# IRsensor_Relay_Controller.net
KiCad netlist of a schematic drawn in Altium Designer
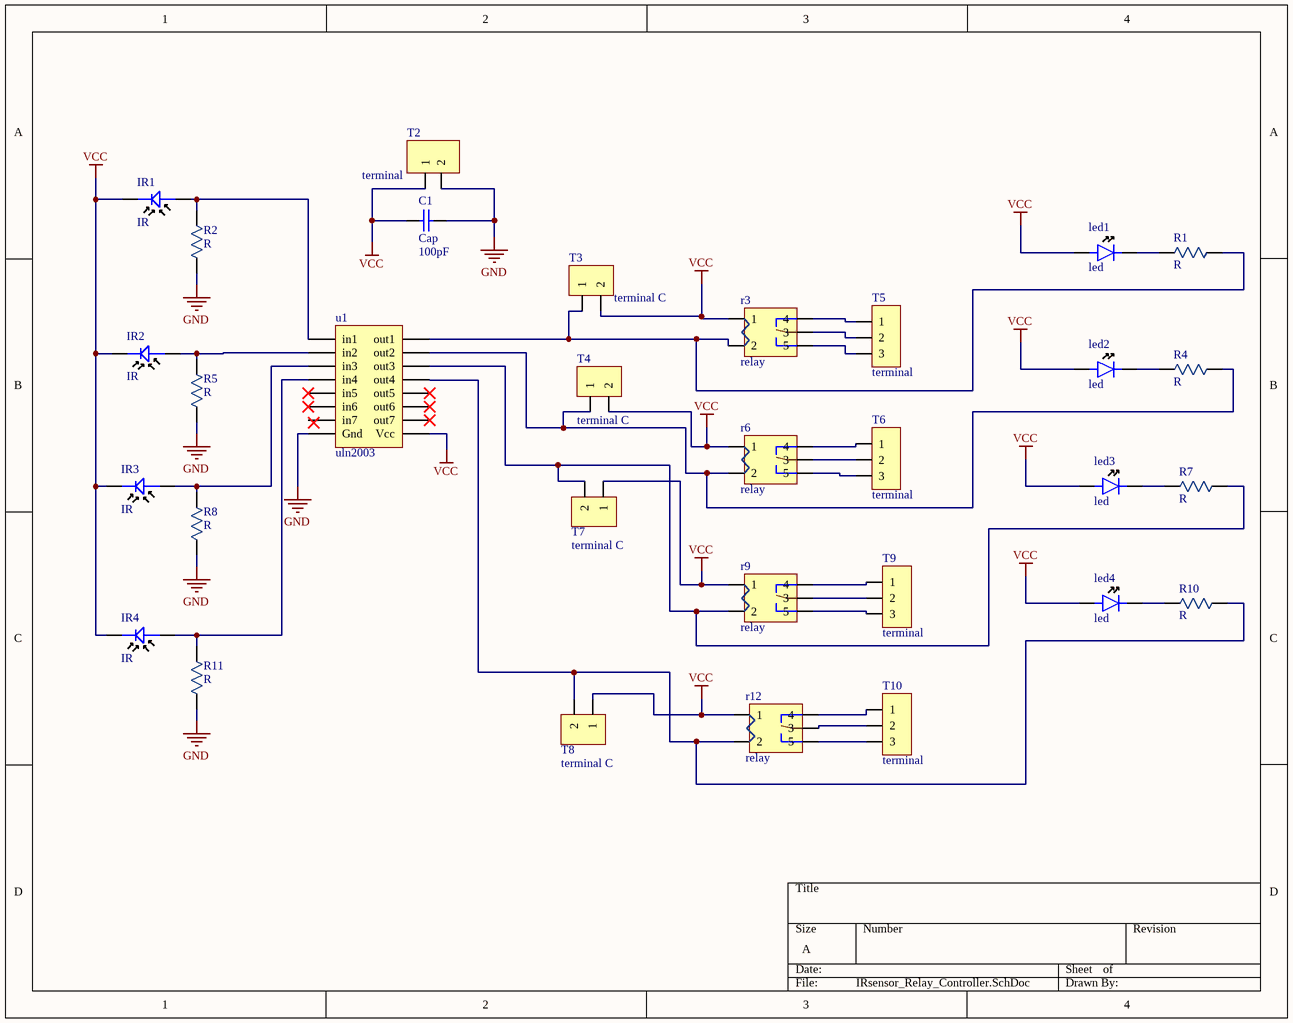
[diagram p0: IRsensor_Relay_Controller.SchDoc]

(export (version "E")
  (design (tool "Eeschema 10.0.6"))
  (components
    (comp (ref "C1")
      (value "Cap")
      (footprint "RAD-0.3")
      (description "Capacitor")
      (fields (field (name "ALTIUM_VALUE") "100pF") (field (name "PUBLISHER") "Altium Limited"))
      (libsource (lib "Miscellaneous Devices") (part "Cap"))
    )
    (comp (ref "IR1")
      (value "IR")
      (footprint "IR sensor")
      (description "EMITTER IR 940NM 100MA RADIAL")
      (fields (field (name "MANUFACTURER") "Everlight") (field (name "MANUFACTURER PART NUMBER") "IR204-A"))
      (libsource (lib "Schlib1") (part "IR204-A"))
    )
    (comp (ref "IR2")
      (value "IR")
      (footprint "IR sensor")
      (description "EMITTER IR 940NM 100MA RADIAL")
      (fields (field (name "MANUFACTURER") "Everlight") (field (name "MANUFACTURER PART NUMBER") "IR204-A"))
      (libsource (lib "Schlib1") (part "IR204-A"))
    )
    (comp (ref "IR3")
      (value "IR")
      (footprint "IR sensor")
      (description "EMITTER IR 940NM 100MA RADIAL")
      (fields (field (name "MANUFACTURER") "Everlight") (field (name "MANUFACTURER PART NUMBER") "IR204-A"))
      (libsource (lib "Schlib1") (part "IR204-A"))
    )
    (comp (ref "IR4")
      (value "IR")
      (footprint "IR sensor")
      (description "EMITTER IR 940NM 100MA RADIAL")
      (fields (field (name "MANUFACTURER") "Everlight") (field (name "MANUFACTURER PART NUMBER") "IR204-A"))
      (libsource (lib "Schlib1") (part "IR204-A"))
    )
    (comp (ref "led1")
      (value "led")
      (footprint "led")
      (description "LED,  5MM,  HIGH EFFICIENCY,  DIFFUSED,  RED")
      (fields (field (name "MANUFACTURER") "Dialight") (field (name "MANUFACTURER PART NUMBER") "521-9240F"))
      (libsource (lib "Schlib1") (part "led"))
    )
    (comp (ref "led2")
      (value "led")
      (footprint "led")
      (description "LED,  5MM,  HIGH EFFICIENCY,  DIFFUSED,  RED")
      (fields (field (name "MANUFACTURER") "Dialight") (field (name "MANUFACTURER PART NUMBER") "521-9240F"))
      (libsource (lib "Schlib1") (part "led"))
    )
    (comp (ref "led3")
      (value "led")
      (footprint "led")
      (description "LED,  5MM,  HIGH EFFICIENCY,  DIFFUSED,  RED")
      (fields (field (name "MANUFACTURER") "Dialight") (field (name "MANUFACTURER PART NUMBER") "521-9240F"))
      (libsource (lib "Schlib1") (part "led"))
    )
    (comp (ref "led4")
      (value "led")
      (footprint "led")
      (description "LED,  5MM,  HIGH EFFICIENCY,  DIFFUSED,  RED")
      (fields (field (name "MANUFACTURER") "Dialight") (field (name "MANUFACTURER PART NUMBER") "521-9240F"))
      (libsource (lib "Schlib1") (part "led"))
    )
    (comp (ref "R1")
      (value "R")
      (footprint "resistor 1/4 watt")
      (description "RES 330 OHM 1/4W 5% AXIAL")
      (fields
        (field (name "MANUFACTURER") "TE Connectivity")
        (field (name "MANUFACTURER PART NUMBER") "CBT25J330R")
      )
      (libsource (lib "Schlib1") (part "resistor 1/4 watt"))
    )
    (comp (ref "R2")
      (value "R")
      (footprint "resistor 1/4 watt")
      (description "RES 330 OHM 1/4W 5% AXIAL")
      (fields
        (field (name "MANUFACTURER") "TE Connectivity")
        (field (name "MANUFACTURER PART NUMBER") "CBT25J330R")
      )
      (libsource (lib "Schlib1") (part "resistor 1/4 watt"))
    )
    (comp (ref "r3")
      (value "relay")
      (footprint "relay 5vdc")
      (fields
        (field (name "MANUFACTURER") "TE Connectivity")
        (field (name "MANUFACTURER PART NUMBER") "V23101-D0007-A201")
      )
      (libsource (lib "Schlib1") (part "relay 5v"))
    )
    (comp (ref "R4")
      (value "R")
      (footprint "resistor 1/4 watt")
      (description "RES 330 OHM 1/4W 5% AXIAL")
      (fields
        (field (name "MANUFACTURER") "TE Connectivity")
        (field (name "MANUFACTURER PART NUMBER") "CBT25J330R")
      )
      (libsource (lib "Schlib1") (part "resistor 1/4 watt"))
    )
    (comp (ref "R5")
      (value "R")
      (footprint "resistor 1/4 watt")
      (description "RES 330 OHM 1/4W 5% AXIAL")
      (fields
        (field (name "MANUFACTURER") "TE Connectivity")
        (field (name "MANUFACTURER PART NUMBER") "CBT25J330R")
      )
      (libsource (lib "Schlib1") (part "resistor 1/4 watt"))
    )
    (comp (ref "r6")
      (value "relay")
      (footprint "relay 5vdc")
      (fields
        (field (name "MANUFACTURER") "TE Connectivity")
        (field (name "MANUFACTURER PART NUMBER") "V23101-D0007-A201")
      )
      (libsource (lib "Schlib1") (part "relay 5v"))
    )
    (comp (ref "R7")
      (value "R")
      (footprint "resistor 1/4 watt")
      (description "RES 330 OHM 1/4W 5% AXIAL")
      (fields
        (field (name "MANUFACTURER") "TE Connectivity")
        (field (name "MANUFACTURER PART NUMBER") "CBT25J330R")
      )
      (libsource (lib "Schlib1") (part "resistor 1/4 watt"))
    )
    (comp (ref "R8")
      (value "R")
      (footprint "resistor 1/4 watt")
      (description "RES 330 OHM 1/4W 5% AXIAL")
      (fields
        (field (name "MANUFACTURER") "TE Connectivity")
        (field (name "MANUFACTURER PART NUMBER") "CBT25J330R")
      )
      (libsource (lib "Schlib1") (part "resistor 1/4 watt"))
    )
    (comp (ref "r9")
      (value "relay")
      (footprint "relay 5vdc")
      (fields
        (field (name "MANUFACTURER") "TE Connectivity")
        (field (name "MANUFACTURER PART NUMBER") "V23101-D0007-A201")
      )
      (libsource (lib "Schlib1") (part "relay 5v"))
    )
    (comp (ref "R10")
      (value "R")
      (footprint "resistor 1/4 watt")
      (description "RES 330 OHM 1/4W 5% AXIAL")
      (fields
        (field (name "MANUFACTURER") "TE Connectivity")
        (field (name "MANUFACTURER PART NUMBER") "CBT25J330R")
      )
      (libsource (lib "Schlib1") (part "resistor 1/4 watt"))
    )
    (comp (ref "R11")
      (value "R")
      (footprint "resistor 1/4 watt")
      (description "RES 330 OHM 1/4W 5% AXIAL")
      (fields
        (field (name "MANUFACTURER") "TE Connectivity")
        (field (name "MANUFACTURER PART NUMBER") "CBT25J330R")
      )
      (libsource (lib "Schlib1") (part "resistor 1/4 watt"))
    )
    (comp (ref "r12")
      (value "relay")
      (footprint "relay 5vdc")
      (fields
        (field (name "MANUFACTURER") "TE Connectivity")
        (field (name "MANUFACTURER PART NUMBER") "V23101-D0007-A201")
      )
      (libsource (lib "Schlib1") (part "relay 5v"))
    )
    (comp (ref "T2")
      (value "terminal")
      (footprint "terminal 2pin")
      (description "PCB Terminal Block 3 Poles, 5 mm Pitch, 691101710003, Würth Elektronik")
      (fields
        (field (name "MANUFACTURER") "Wurth Electronics")
        (field (name "MANUFACTURER PART NUMBER") "691101710003")
      )
      (libsource (lib "Schlib1") (part "terminal 2pin"))
    )
    (comp (ref "T3")
      (value "terminal C")
      (footprint "terminal C 2pin")
      (description ".100 TERMINAL ASSEMBLY")
      (fields
        (field (name "MANUFACTURER") "Samtec")
        (field (name "MANUFACTURER PART NUMBER") "IPL1-102-01-S-S-RA-K")
      )
      (libsource (lib "") (part "terminal Cu_1"))
    )
    (comp (ref "T4")
      (value "terminal C")
      (footprint "terminal C 2pin")
      (description ".100 TERMINAL ASSEMBLY")
      (fields
        (field (name "MANUFACTURER") "Samtec")
        (field (name "MANUFACTURER PART NUMBER") "IPL1-102-01-S-S-RA-K")
      )
      (libsource (lib "") (part "terminal Cu_1"))
    )
    (comp (ref "T5")
      (value "terminal")
      (footprint "terminal 3pin")
      (description "Conn Mini-Power Terminal Strip HDR 12 POS 2.54mm Solder ST SMD 12 Terminal 1 Port")
      (fields
        (field (name "MANUFACTURER") "Samtec")
        (field (name "MANUFACTURER PART NUMBER") "IPL1-106-02-L-D-K")
      )
      (libsource (lib "Schlib1") (part "terminal 3pin"))
    )
    (comp (ref "T6")
      (value "terminal")
      (footprint "terminal 3pin")
      (description "Conn Mini-Power Terminal Strip HDR 12 POS 2.54mm Solder ST SMD 12 Terminal 1 Port")
      (fields
        (field (name "MANUFACTURER") "Samtec")
        (field (name "MANUFACTURER PART NUMBER") "IPL1-106-02-L-D-K")
      )
      (libsource (lib "Schlib1") (part "terminal 3pin"))
    )
    (comp (ref "T7")
      (value "terminal C")
      (footprint "terminal C 2pin")
      (description ".100 TERMINAL ASSEMBLY")
      (fields
        (field (name "MANUFACTURER") "Samtec")
        (field (name "MANUFACTURER PART NUMBER") "IPL1-102-01-S-S-RA-K")
      )
      (libsource (lib "Schlib1") (part "terminal Cu"))
    )
    (comp (ref "T8")
      (value "terminal C")
      (footprint "terminal C 2pin")
      (description ".100 TERMINAL ASSEMBLY")
      (fields
        (field (name "MANUFACTURER") "Samtec")
        (field (name "MANUFACTURER PART NUMBER") "IPL1-102-01-S-S-RA-K")
      )
      (libsource (lib "Schlib1") (part "terminal Cu"))
    )
    (comp (ref "T9")
      (value "terminal")
      (footprint "terminal 3pin")
      (description "Conn Mini-Power Terminal Strip HDR 12 POS 2.54mm Solder ST SMD 12 Terminal 1 Port")
      (fields
        (field (name "MANUFACTURER") "Samtec")
        (field (name "MANUFACTURER PART NUMBER") "IPL1-106-02-L-D-K")
      )
      (libsource (lib "Schlib1") (part "terminal 3pin"))
    )
    (comp (ref "T10")
      (value "terminal")
      (footprint "terminal 3pin")
      (description "Conn Mini-Power Terminal Strip HDR 12 POS 2.54mm Solder ST SMD 12 Terminal 1 Port")
      (fields
        (field (name "MANUFACTURER") "Samtec")
        (field (name "MANUFACTURER PART NUMBER") "IPL1-106-02-L-D-K")
      )
      (libsource (lib "Schlib1") (part "terminal 3pin"))
    )
    (comp (ref "u1")
      (value "uln2003")
      (footprint "uln2003")
      (description "TEXAS INSTRUMENTS - ULN2003ADR - Bipolar Transistor Array, Darlington, NPN, 50 V, 350 mA, SOIC")
      (fields
        (field (name "MANUFACTURER") "Texas Instruments")
        (field (name "MANUFACTURER PART NUMBER") "ULN2003ADR")
      )
      (libsource (lib "Schlib1") (part "ULN2003ADR"))
    )
  )
  (nets
    (net (code "1") (name "GND") (class "Default")
      (node (ref "C1") (pin "2") (pinfunction "2_2") (pintype "passive"))
      (node (ref "R11") (pin "2") (pinfunction "2_2") (pintype "passive"))
      (node (ref "R2") (pin "2") (pinfunction "2_2") (pintype "passive"))
      (node (ref "R5") (pin "2") (pinfunction "2_2") (pintype "passive"))
      (node (ref "R8") (pin "2") (pinfunction "2_2") (pintype "passive"))
      (node (ref "T2") (pin "2") (pinfunction "2_2") (pintype "passive"))
      (node (ref "u1") (pin "Vcc") (pinfunction "Gnd_Vcc") (pintype "passive"))
    )
    (net (code "2") (name "Net-(IR1-Pad+)") (class "Default")
      (node (ref "IR1") (pin "+") (pinfunction "+_+") (pintype "passive"))
      (node (ref "R2") (pin "1") (pinfunction "1_1") (pintype "passive"))
      (node (ref "u1") (pin "in1") (pinfunction "in1_in1") (pintype "passive"))
    )
    (net (code "3") (name "Net-(IR2-Pad+)") (class "Default")
      (node (ref "IR2") (pin "+") (pinfunction "+_+") (pintype "passive"))
      (node (ref "R5") (pin "1") (pinfunction "1_1") (pintype "passive"))
      (node (ref "u1") (pin "in2") (pinfunction "in2_in2") (pintype "passive"))
    )
    (net (code "4") (name "Net-(IR3-Pad+)") (class "Default")
      (node (ref "IR3") (pin "+") (pinfunction "+_+") (pintype "passive"))
      (node (ref "R8") (pin "1") (pinfunction "1_1") (pintype "passive"))
      (node (ref "u1") (pin "in3") (pinfunction "in3_in3") (pintype "passive"))
    )
    (net (code "5") (name "Net-(IR4-Pad+)") (class "Default")
      (node (ref "IR4") (pin "+") (pinfunction "+_+") (pintype "passive"))
      (node (ref "R11") (pin "1") (pinfunction "1_1") (pintype "passive"))
      (node (ref "u1") (pin "in4") (pinfunction "in4_in4") (pintype "passive"))
    )
    (net (code "6") (name "Net-(R1-Pad1)") (class "Default")
      (node (ref "R1") (pin "1") (pinfunction "1_1") (pintype "passive"))
      (node (ref "led1") (pin "-") (pinfunction "-_-") (pintype "passive"))
    )
    (net (code "7") (name "Net-(R1-Pad2)") (class "Default")
      (node (ref "R1") (pin "2") (pinfunction "2_2") (pintype "passive"))
      (node (ref "T3") (pin "1") (pinfunction "1_1") (pintype "passive"))
      (node (ref "r3") (pin "2") (pinfunction "2_2") (pintype "passive"))
      (node (ref "u1") (pin "out1") (pinfunction "out1_out1") (pintype "passive"))
    )
    (net (code "8") (name "Net-(R4-Pad1)") (class "Default")
      (node (ref "R4") (pin "1") (pinfunction "1_1") (pintype "passive"))
      (node (ref "led2") (pin "-") (pinfunction "-_-") (pintype "passive"))
    )
    (net (code "9") (name "Net-(R4-Pad2)") (class "Default")
      (node (ref "R4") (pin "2") (pinfunction "2_2") (pintype "passive"))
      (node (ref "T4") (pin "1") (pinfunction "1_1") (pintype "passive"))
      (node (ref "r6") (pin "2") (pinfunction "2_2") (pintype "passive"))
      (node (ref "u1") (pin "out2") (pinfunction "out2_out2") (pintype "passive"))
    )
    (net (code "10") (name "Net-(R7-Pad1)") (class "Default")
      (node (ref "R7") (pin "1") (pinfunction "1_1") (pintype "passive"))
      (node (ref "led3") (pin "-") (pinfunction "-_-") (pintype "passive"))
    )
    (net (code "11") (name "Net-(R7-Pad2)") (class "Default")
      (node (ref "R7") (pin "2") (pinfunction "2_2") (pintype "passive"))
      (node (ref "T7") (pin "2") (pinfunction "2_2") (pintype "passive"))
      (node (ref "r9") (pin "2") (pinfunction "2_2") (pintype "passive"))
      (node (ref "u1") (pin "out3") (pinfunction "out3_out3") (pintype "passive"))
    )
    (net (code "12") (name "Net-(R10-Pad1)") (class "Default")
      (node (ref "R10") (pin "1") (pinfunction "1_1") (pintype "passive"))
      (node (ref "led4") (pin "-") (pinfunction "-_-") (pintype "passive"))
    )
    (net (code "13") (name "Net-(R10-Pad2)") (class "Default")
      (node (ref "R10") (pin "2") (pinfunction "2_2") (pintype "passive"))
      (node (ref "T8") (pin "2") (pinfunction "2_2") (pintype "passive"))
      (node (ref "r12") (pin "2") (pinfunction "2_2") (pintype "passive"))
      (node (ref "u1") (pin "out4") (pinfunction "out4_out4") (pintype "passive"))
    )
    (net (code "14") (name "Net-(T5-Pad1)") (class "Default")
      (node (ref "T5") (pin "1") (pinfunction "1_1") (pintype "passive"))
      (node (ref "r3") (pin "4") (pinfunction "4_4") (pintype "passive"))
    )
    (net (code "15") (name "Net-(T5-Pad2)") (class "Default")
      (node (ref "T5") (pin "2") (pinfunction "2_2") (pintype "passive"))
      (node (ref "r3") (pin "3") (pinfunction "3_3") (pintype "passive"))
    )
    (net (code "16") (name "Net-(T5-Pad3)") (class "Default")
      (node (ref "T5") (pin "3") (pinfunction "3_3") (pintype "passive"))
      (node (ref "r3") (pin "5") (pinfunction "5_5") (pintype "passive"))
    )
    (net (code "17") (name "Net-(T6-Pad1)") (class "Default")
      (node (ref "T6") (pin "1") (pinfunction "1_1") (pintype "passive"))
      (node (ref "r6") (pin "4") (pinfunction "4_4") (pintype "passive"))
    )
    (net (code "18") (name "Net-(T6-Pad2)") (class "Default")
      (node (ref "T6") (pin "2") (pinfunction "2_2") (pintype "passive"))
      (node (ref "r6") (pin "3") (pinfunction "3_3") (pintype "passive"))
    )
    (net (code "19") (name "Net-(T6-Pad3)") (class "Default")
      (node (ref "T6") (pin "3") (pinfunction "3_3") (pintype "passive"))
      (node (ref "r6") (pin "5") (pinfunction "5_5") (pintype "passive"))
    )
    (net (code "20") (name "Net-(T9-Pad1)") (class "Default")
      (node (ref "T9") (pin "1") (pinfunction "1_1") (pintype "passive"))
      (node (ref "r9") (pin "4") (pinfunction "4_4") (pintype "passive"))
    )
    (net (code "21") (name "Net-(T9-Pad2)") (class "Default")
      (node (ref "T9") (pin "2") (pinfunction "2_2") (pintype "passive"))
      (node (ref "r9") (pin "3") (pinfunction "3_3") (pintype "passive"))
    )
    (net (code "22") (name "Net-(T9-Pad3)") (class "Default")
      (node (ref "T9") (pin "3") (pinfunction "3_3") (pintype "passive"))
      (node (ref "r9") (pin "5") (pinfunction "5_5") (pintype "passive"))
    )
    (net (code "23") (name "Net-(T10-Pad1)") (class "Default")
      (node (ref "T10") (pin "1") (pinfunction "1_1") (pintype "passive"))
      (node (ref "r12") (pin "4") (pinfunction "4_4") (pintype "passive"))
    )
    (net (code "24") (name "Net-(T10-Pad2)") (class "Default")
      (node (ref "T10") (pin "2") (pinfunction "2_2") (pintype "passive"))
      (node (ref "r12") (pin "3") (pinfunction "3_3") (pintype "passive"))
    )
    (net (code "25") (name "Net-(T10-Pad3)") (class "Default")
      (node (ref "T10") (pin "3") (pinfunction "3_3") (pintype "passive"))
      (node (ref "r12") (pin "5") (pinfunction "5_5") (pintype "passive"))
    )
    (net (code "26") (name "VCC") (class "Default")
      (node (ref "C1") (pin "1") (pinfunction "1_1") (pintype "passive"))
      (node (ref "IR1") (pin "-") (pinfunction "-_-") (pintype "passive"))
      (node (ref "IR2") (pin "-") (pinfunction "-_-") (pintype "passive"))
      (node (ref "IR3") (pin "-") (pinfunction "-_-") (pintype "passive"))
      (node (ref "IR4") (pin "-") (pinfunction "-_-") (pintype "passive"))
      (node (ref "T2") (pin "1") (pinfunction "1_1") (pintype "passive"))
      (node (ref "T3") (pin "2") (pinfunction "2_2") (pintype "passive"))
      (node (ref "T4") (pin "2") (pinfunction "2_2") (pintype "passive"))
      (node (ref "T7") (pin "1") (pinfunction "1_1") (pintype "passive"))
      (node (ref "T8") (pin "1") (pinfunction "1_1") (pintype "passive"))
      (node (ref "led1") (pin "+") (pinfunction "+_+") (pintype "passive"))
      (node (ref "led2") (pin "+") (pinfunction "+_+") (pintype "passive"))
      (node (ref "led3") (pin "+") (pinfunction "+_+") (pintype "passive"))
      (node (ref "led4") (pin "+") (pinfunction "+_+") (pintype "passive"))
      (node (ref "r12") (pin "1") (pinfunction "1_1") (pintype "passive"))
      (node (ref "r3") (pin "1") (pinfunction "1_1") (pintype "passive"))
      (node (ref "r6") (pin "1") (pinfunction "1_1") (pintype "passive"))
      (node (ref "r9") (pin "1") (pinfunction "1_1") (pintype "passive"))
      (node (ref "u1") (pin "Vcc") (pinfunction "Vcc_Vcc") (pintype "passive"))
    )
    (net (code "27") (name "unconnected-(u1-Padin5)") (class "Default")
      (node (ref "u1") (pin "in5") (pinfunction "in5_in5") (pintype "passive+no_connect"))
    )
    (net (code "28") (name "unconnected-(u1-Padin6)") (class "Default")
      (node (ref "u1") (pin "in6") (pinfunction "in6_in6") (pintype "passive+no_connect"))
    )
    (net (code "29") (name "unconnected-(u1-Padin7)") (class "Default")
      (node (ref "u1") (pin "in7") (pinfunction "in7_in7") (pintype "passive"))
    )
    (net (code "30") (name "unconnected-(u1-Padout5)") (class "Default")
      (node (ref "u1") (pin "out5") (pinfunction "out5_out5") (pintype "passive+no_connect"))
    )
    (net (code "31") (name "unconnected-(u1-Padout6)") (class "Default")
      (node (ref "u1") (pin "out6") (pinfunction "out6_out6") (pintype "passive+no_connect"))
    )
    (net (code "32") (name "unconnected-(u1-Padout7)") (class "Default")
      (node (ref "u1") (pin "out7") (pinfunction "out7_out7") (pintype "passive+no_connect"))
    )
  )
)
